# motor-board.net
KiCad netlist of a schematic drawn in EAGLE
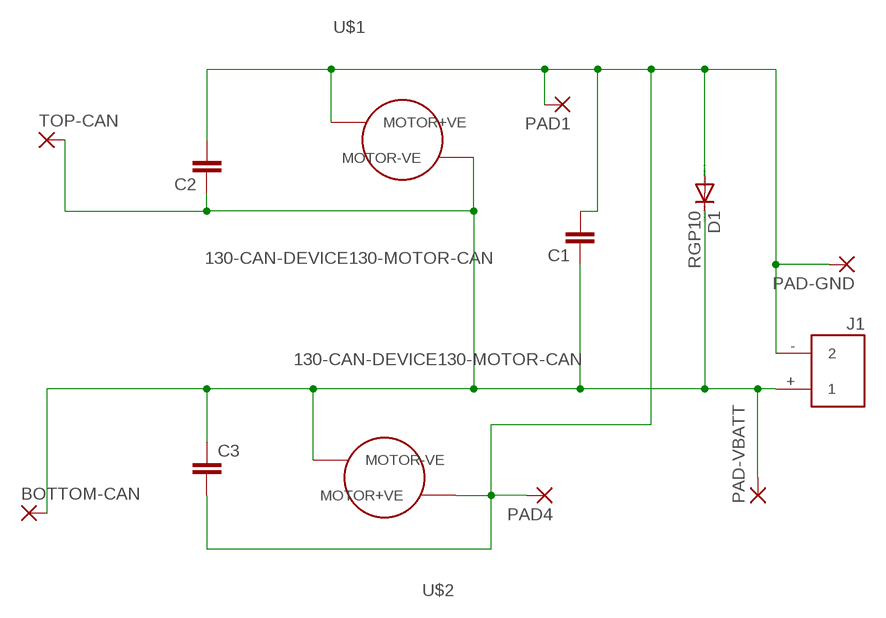
[diagram p0: schematic, sheet 1]

(export (version "E")
  (design (tool "Eeschema 10.0.6"))
  (components
    (comp (ref "BOTTOM-CAN")
      (value "WIREPADSMD1,27-254")
      (footprint "eagle-import:SMD1,27-2,54")
      (libsource (lib "eagle-import") (part "WIREPADSMD1,27-254"))
    )
    (comp (ref "C1")
      (value "C-EU050-024X044")
      (footprint "eagle-import:C050-024X044")
      (libsource (lib "eagle-import") (part "C-EU050-024X044"))
    )
    (comp (ref "C2")
      (value "C-EU050-024X044")
      (footprint "eagle-import:C050-024X044")
      (libsource (lib "eagle-import") (part "C-EU050-024X044"))
    )
    (comp (ref "C3")
      (value "C-EU050-024X044")
      (footprint "eagle-import:C050-024X044")
      (libsource (lib "eagle-import") (part "C-EU050-024X044"))
    )
    (comp (ref "D1")
      (value "RGP10")
      (footprint "eagle-import:DO41-10")
      (libsource (lib "eagle-import") (part "RGP10"))
    )
    (comp (ref "J1")
      (value "XT60_FEMALE")
      (footprint "eagle-import:XT60_FEMALE")
      (libsource (lib "eagle-import") (part "XT60_FEMALE"))
    )
    (comp (ref "PAD-GND")
      (value "WIREPAD3,81/1,4")
      (footprint "eagle-import:3,81_1,4")
      (libsource (lib "eagle-import") (part "WIREPAD3,81/1,4"))
    )
    (comp (ref "PAD-VBATT")
      (value "WIREPAD3,81/1,4")
      (footprint "eagle-import:3,81_1,4")
      (libsource (lib "eagle-import") (part "WIREPAD3,81/1,4"))
    )
    (comp (ref "PAD1")
      (value "WIREPADSMD1,27-254")
      (footprint "eagle-import:SMD1,27-2,54")
      (libsource (lib "eagle-import") (part "WIREPADSMD1,27-254"))
    )
    (comp (ref "PAD4")
      (value "WIREPADSMD1,27-254")
      (footprint "eagle-import:SMD1,27-2,54")
      (libsource (lib "eagle-import") (part "WIREPADSMD1,27-254"))
    )
    (comp (ref "TOP-CAN")
      (value "WIREPADSMD1,27-254")
      (footprint "eagle-import:SMD1,27-2,54")
      (libsource (lib "eagle-import") (part "WIREPADSMD1,27-254"))
    )
    (comp (ref "U$1")
      (value "130-CAN-DEVICE130-MOTOR-CAN")
      (footprint "eagle-import:130-MOTOR-CAN")
      (libsource (lib "eagle-import") (part "130-CAN-DEVICE130-MOTOR-CAN"))
    )
    (comp (ref "U$2")
      (value "130-CAN-DEVICE130-MOTOR-CAN")
      (footprint "eagle-import:130-MOTOR-CAN")
      (libsource (lib "eagle-import") (part "130-CAN-DEVICE130-MOTOR-CAN"))
    )
  )
  (nets
    (net (code "1") (name "Net-(BOTTOM-CAN-P)") (class "Default")
      (node (ref "BOTTOM-CAN") (pin "1") (pinfunction "P_1") (pintype "passive"))
      (node (ref "C1") (pin "1") (pinfunction "1_1") (pintype "passive"))
      (node (ref "C2") (pin "1") (pinfunction "1_1") (pintype "passive"))
      (node (ref "C3") (pin "1") (pinfunction "1_1") (pintype "passive"))
      (node (ref "D1") (pin "C") (pinfunction "C_C") (pintype "passive"))
      (node (ref "J1") (pin "+") (pinfunction "1_+") (pintype "bidirectional"))
      (node (ref "PAD-VBATT") (pin "1") (pinfunction "P_1") (pintype "passive"))
      (node (ref "TOP-CAN") (pin "1") (pinfunction "P_1") (pintype "passive"))
      (node (ref "U$1") (pin "MOTOR-VE") (pinfunction "MOTOR-VE_MOTOR-VE") (pintype "bidirectional"))
      (node (ref "U$2") (pin "MOTOR-VE") (pinfunction "MOTOR-VE_MOTOR-VE") (pintype "bidirectional"))
    )
    (net (code "2") (name "Net-(J1-2)") (class "Default")
      (node (ref "C1") (pin "2") (pinfunction "2_2") (pintype "passive"))
      (node (ref "C2") (pin "2") (pinfunction "2_2") (pintype "passive"))
      (node (ref "C3") (pin "2") (pinfunction "2_2") (pintype "passive"))
      (node (ref "D1") (pin "A") (pinfunction "A_A") (pintype "passive"))
      (node (ref "J1") (pin "-") (pinfunction "2_-") (pintype "bidirectional"))
      (node (ref "PAD-GND") (pin "1") (pinfunction "P_1") (pintype "passive"))
      (node (ref "PAD1") (pin "1") (pinfunction "P_1") (pintype "passive"))
      (node (ref "PAD4") (pin "1") (pinfunction "P_1") (pintype "passive"))
      (node (ref "U$1") (pin "MOTOR+VE") (pinfunction "MOTOR+VE_MOTOR+VE") (pintype "bidirectional"))
      (node (ref "U$2") (pin "MOTOR+VE") (pinfunction "MOTOR+VE_MOTOR+VE") (pintype "bidirectional"))
    )
  )
)
